# Schema_Electrica.net
KiCad netlist of a schematic drawn in EAGLE
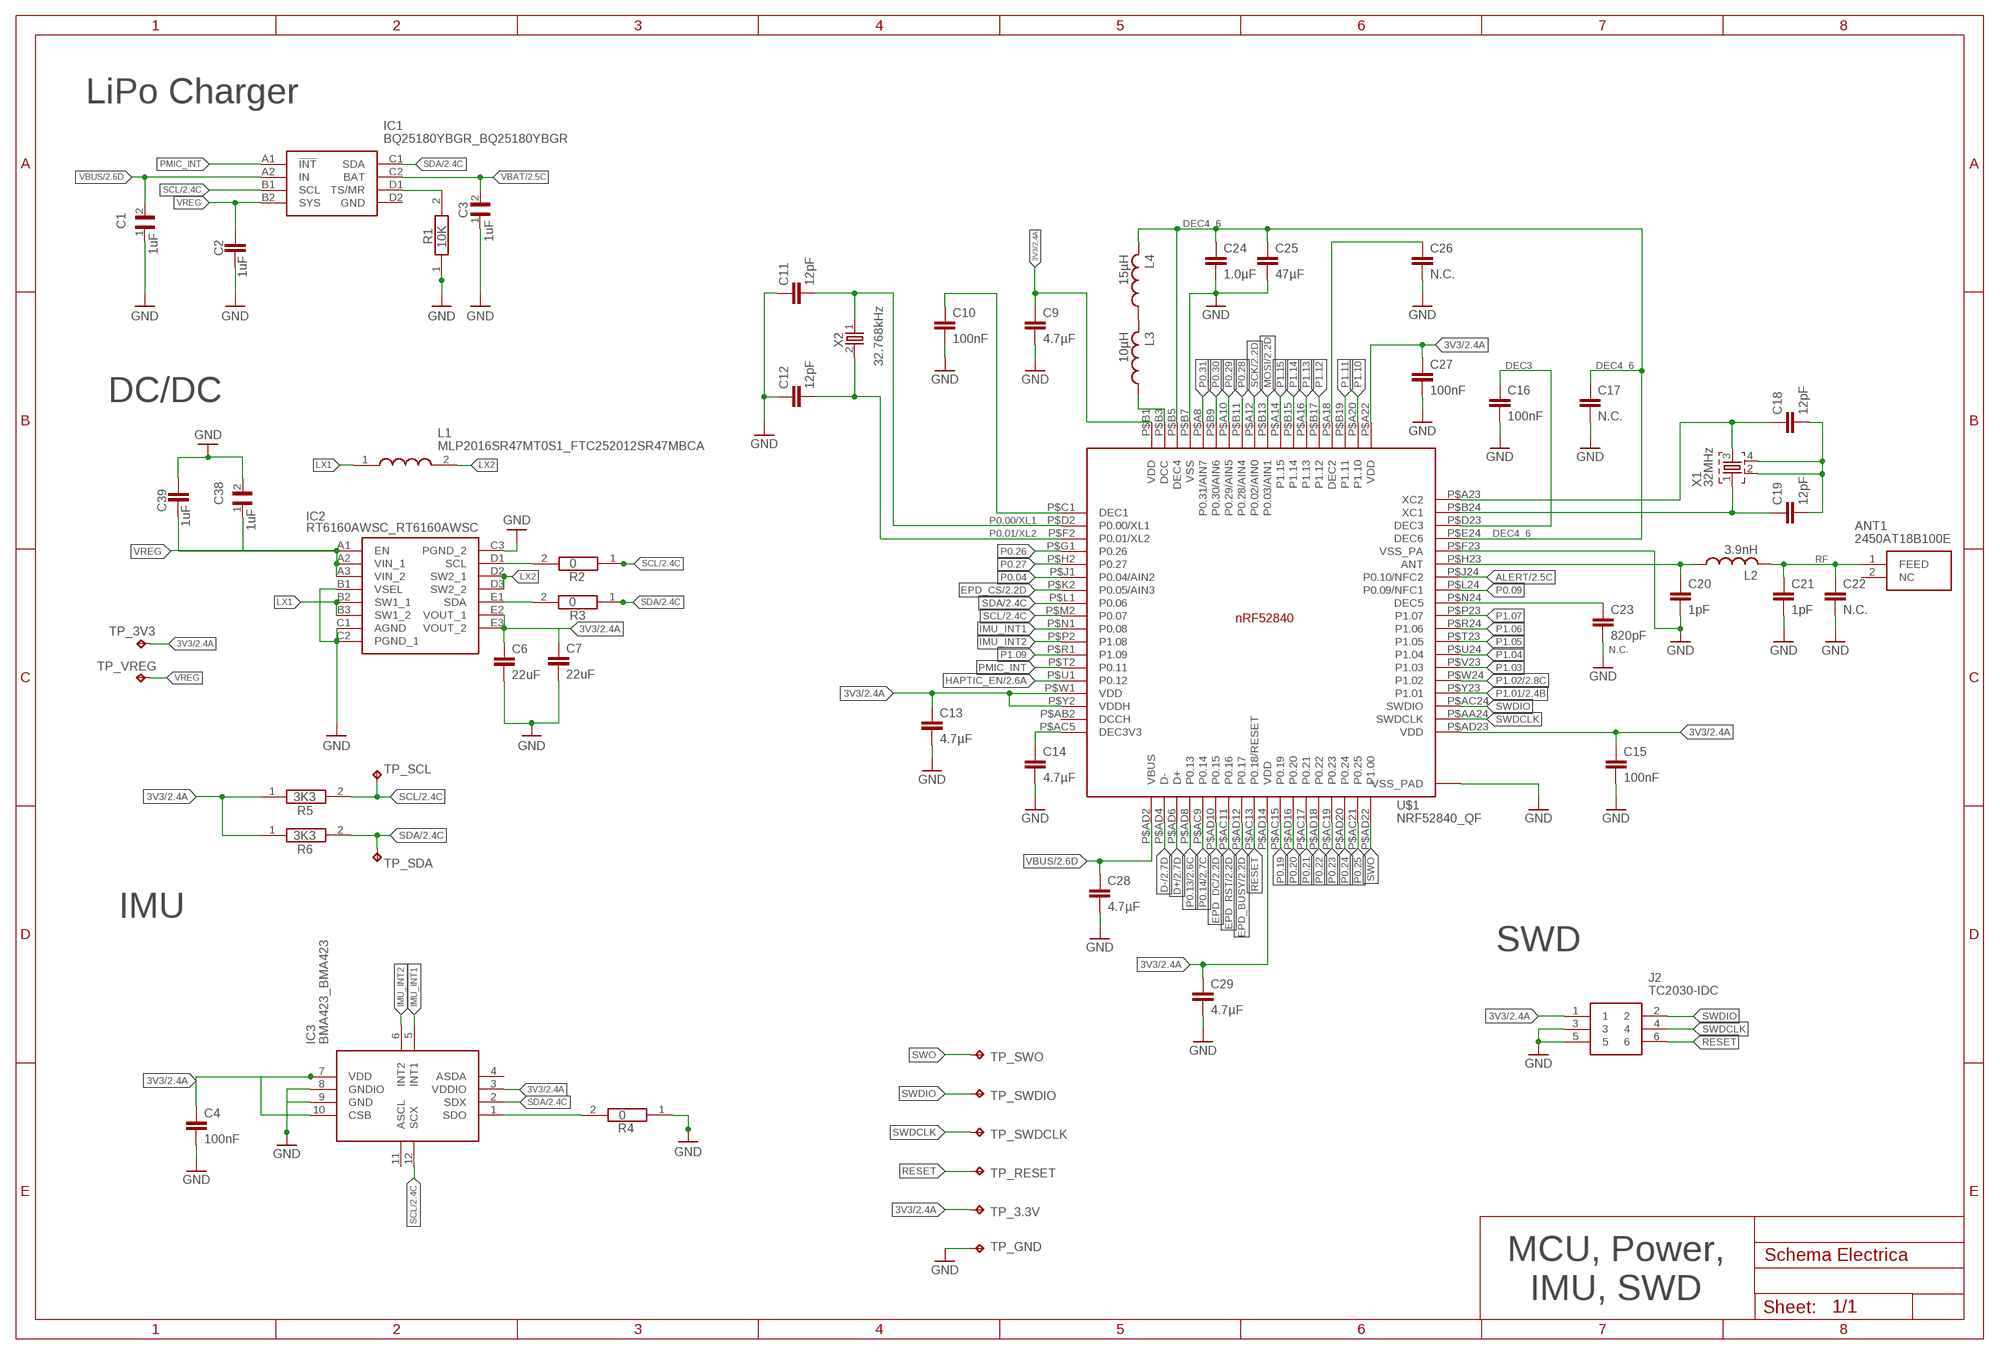
[diagram p0: schematic, sheet 1, part 1 of 2]
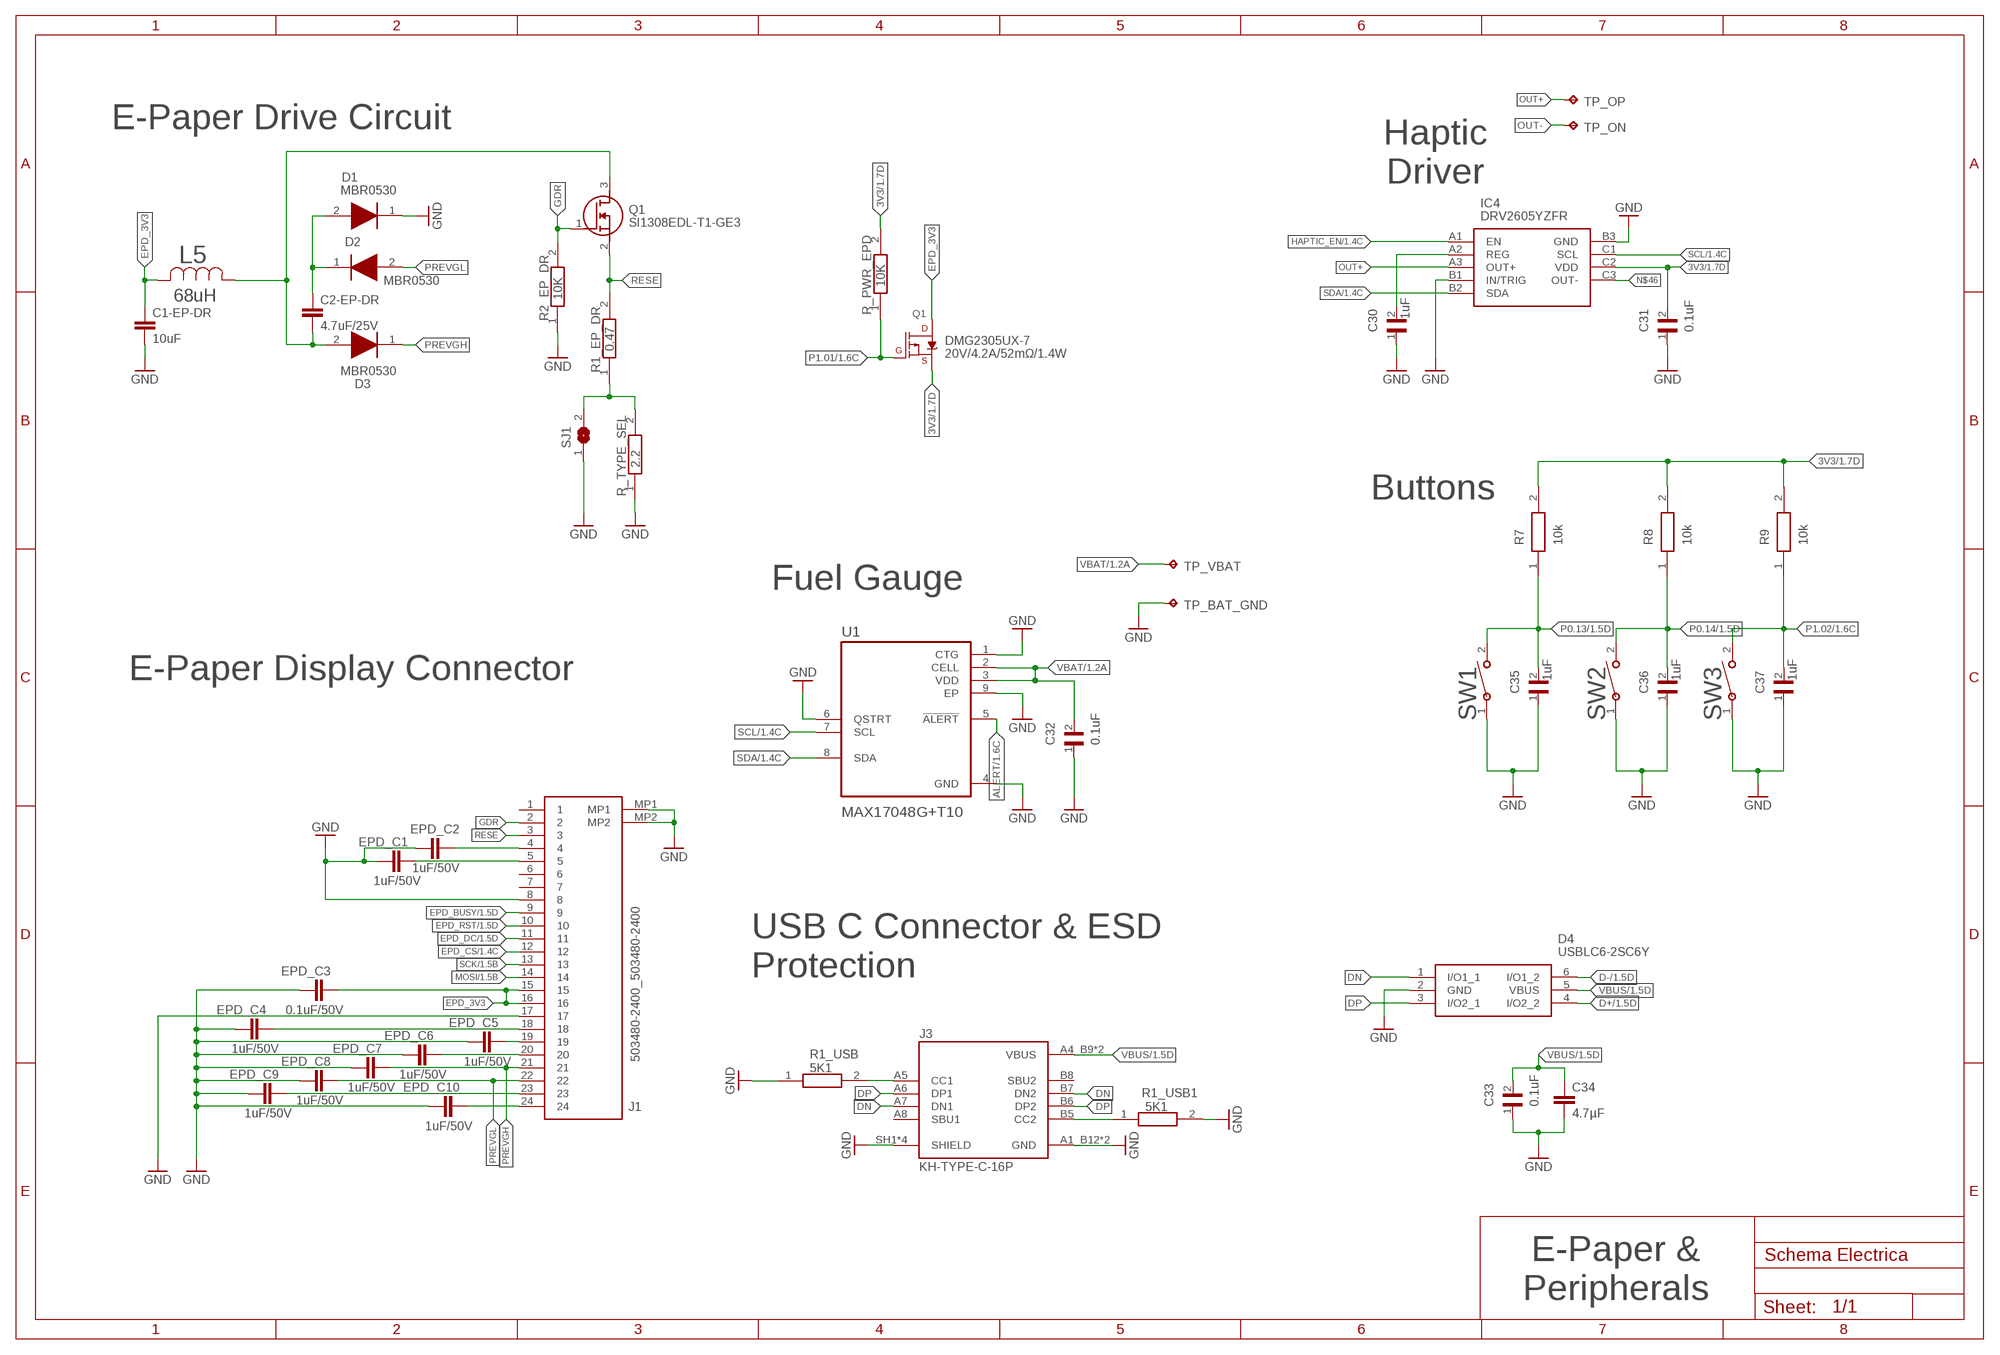
[diagram p1: schematic, sheet 1, part 2 of 2]

(export (version "E")
  (design (tool "Eeschema 10.0.6"))
  (components
    (comp (ref "ANT1")
      (value "2450AT18B100E")
      (footprint "eagle-import:2450AT18B100E_ANTC3216X140N")
      (fields (field (name "MOUSER_PART_NUMBER") "609-2450AT18B100E"))
      (libsource (lib "eagle-import") (part "2450AT18B100E_2450AT18B100E"))
    )
    (comp (ref "C1")
      (value "1uF")
      (footprint "eagle-import:GRM011R60J152KE01L_1_0201")
      (libsource (lib "eagle-import") (part "GRM011R60J152KE01L_1_GRM011R60J152KE01L"))
    )
    (comp (ref "C1-EP-DR")
      (value "10uF")
      (footprint "eagle-import:PERFECT_0402_0402")
      (libsource (lib "eagle-import") (part "PERFECT_0402_CAP_0402"))
    )
    (comp (ref "C2")
      (value "1uF")
      (footprint "eagle-import:PERFECT_0402_0402")
      (libsource (lib "eagle-import") (part "PERFECT_0402_CAP_0402"))
    )
    (comp (ref "C2-EP-DR")
      (value "4.7uF/25V")
      (footprint "eagle-import:PERFECT_0402_0402")
      (libsource (lib "eagle-import") (part "PERFECT_0402_CAP_0402"))
    )
    (comp (ref "C3")
      (value "1uF")
      (footprint "eagle-import:GRM011R60J152KE01L_1_0201")
      (libsource (lib "eagle-import") (part "GRM011R60J152KE01L_1_GRM011R60J152KE01L"))
    )
    (comp (ref "C4")
      (value "100nF")
      (footprint "eagle-import:PERFECT_0402_0402")
      (libsource (lib "eagle-import") (part "PERFECT_0402_CAP_0402"))
    )
    (comp (ref "C6")
      (value "22uF")
      (footprint "eagle-import:PERFECT_0402_0402")
      (libsource (lib "eagle-import") (part "PERFECT_0402_CAP_0402"))
    )
    (comp (ref "C7")
      (value "22uF")
      (footprint "eagle-import:PERFECT_0402_0402")
      (libsource (lib "eagle-import") (part "PERFECT_0402_CAP_0402"))
    )
    (comp (ref "C9")
      (value "4.7µF")
      (footprint "eagle-import:PERFECT_0402_0402")
      (libsource (lib "eagle-import") (part "PERFECT_0402_CAP_0402"))
    )
    (comp (ref "C10")
      (value "100nF")
      (footprint "eagle-import:PERFECT_0402_0402")
      (libsource (lib "eagle-import") (part "PERFECT_0402_CAP_0402"))
    )
    (comp (ref "C11")
      (value "12pF")
      (footprint "eagle-import:PERFECT_0402_0402")
      (libsource (lib "eagle-import") (part "PERFECT_0402_CAP_0402"))
    )
    (comp (ref "C12")
      (value "12pF")
      (footprint "eagle-import:PERFECT_0402_0402")
      (libsource (lib "eagle-import") (part "PERFECT_0402_CAP_0402"))
    )
    (comp (ref "C13")
      (value "4.7µF")
      (footprint "eagle-import:PERFECT_0402_0402")
      (libsource (lib "eagle-import") (part "PERFECT_0402_CAP_0402"))
    )
    (comp (ref "C14")
      (value "4.7µF")
      (footprint "eagle-import:PERFECT_0402_0402")
      (libsource (lib "eagle-import") (part "PERFECT_0402_CAP_0402"))
    )
    (comp (ref "C15")
      (value "100nF")
      (footprint "eagle-import:PERFECT_0402_0402")
      (libsource (lib "eagle-import") (part "PERFECT_0402_CAP_0402"))
    )
    (comp (ref "C16")
      (value "100nF")
      (footprint "eagle-import:PERFECT_0402_0402")
      (libsource (lib "eagle-import") (part "PERFECT_0402_CAP_0402"))
    )
    (comp (ref "C17")
      (value "N.C.")
      (footprint "eagle-import:PERFECT_0402_0402")
      (libsource (lib "eagle-import") (part "PERFECT_0402_CAP_0402"))
    )
    (comp (ref "C18")
      (value "12pF")
      (footprint "eagle-import:PERFECT_0402_0402")
      (libsource (lib "eagle-import") (part "PERFECT_0402_CAP_0402"))
    )
    (comp (ref "C19")
      (value "12pF")
      (footprint "eagle-import:PERFECT_0402_0402")
      (libsource (lib "eagle-import") (part "PERFECT_0402_CAP_0402"))
    )
    (comp (ref "C20")
      (value "1pF")
      (footprint "eagle-import:PERFECT_0402_0402")
      (libsource (lib "eagle-import") (part "PERFECT_0402_CAP_0402"))
    )
    (comp (ref "C21")
      (value "1pF")
      (footprint "eagle-import:PERFECT_0402_0402")
      (libsource (lib "eagle-import") (part "PERFECT_0402_CAP_0402"))
    )
    (comp (ref "C22")
      (value "N.C.")
      (footprint "eagle-import:PERFECT_0402_0402")
      (libsource (lib "eagle-import") (part "PERFECT_0402_CAP_0402"))
    )
    (comp (ref "C23")
      (value "820pF")
      (footprint "eagle-import:PERFECT_0402_0402")
      (libsource (lib "eagle-import") (part "PERFECT_0402_CAP_0402"))
    )
    (comp (ref "C24")
      (value "1.0µF")
      (footprint "eagle-import:PERFECT_0402_0402")
      (libsource (lib "eagle-import") (part "PERFECT_0402_CAP_0402"))
    )
    (comp (ref "C25")
      (value "47µF")
      (footprint "eagle-import:PERFECT_0402_0402")
      (libsource (lib "eagle-import") (part "PERFECT_0402_CAP_0402"))
    )
    (comp (ref "C26")
      (value "N.C.")
      (footprint "eagle-import:PERFECT_0402_0402")
      (libsource (lib "eagle-import") (part "PERFECT_0402_CAP_0402"))
    )
    (comp (ref "C27")
      (value "100nF")
      (footprint "eagle-import:PERFECT_0402_0402")
      (libsource (lib "eagle-import") (part "PERFECT_0402_CAP_0402"))
    )
    (comp (ref "C28")
      (value "4.7µF")
      (footprint "eagle-import:PERFECT_0402_0402")
      (libsource (lib "eagle-import") (part "PERFECT_0402_CAP_0402"))
    )
    (comp (ref "C29")
      (value "4.7µF")
      (footprint "eagle-import:PERFECT_0402_0402")
      (libsource (lib "eagle-import") (part "PERFECT_0402_CAP_0402"))
    )
    (comp (ref "C30")
      (value "1uF")
      (footprint "eagle-import:GRM011R60J152KE01L_1_0201")
      (libsource (lib "eagle-import") (part "GRM011R60J152KE01L_1_GRM011R60J152KE01L"))
    )
    (comp (ref "C31")
      (value "0.1uF")
      (footprint "eagle-import:GRM011R60J152KE01L_1_0201")
      (libsource (lib "eagle-import") (part "GRM011R60J152KE01L_1_GRM011R60J152KE01L"))
    )
    (comp (ref "C32")
      (value "0.1uF")
      (footprint "eagle-import:GRM011R60J152KE01L_1_0201")
      (libsource (lib "eagle-import") (part "GRM011R60J152KE01L_1_GRM011R60J152KE01L"))
    )
    (comp (ref "C33")
      (value "0.1uF")
      (footprint "eagle-import:GRM011R60J152KE01L_1_0201")
      (libsource (lib "eagle-import") (part "GRM011R60J152KE01L_1_GRM011R60J152KE01L"))
    )
    (comp (ref "C34")
      (value "4.7µF")
      (footprint "eagle-import:PERFECT_0402_0402")
      (libsource (lib "eagle-import") (part "PERFECT_0402_CAP_0402"))
    )
    (comp (ref "C35")
      (value "1uF")
      (footprint "eagle-import:GRM011R60J152KE01L_1_0201")
      (libsource (lib "eagle-import") (part "GRM011R60J152KE01L_1_GRM011R60J152KE01L"))
    )
    (comp (ref "C36")
      (value "1uF")
      (footprint "eagle-import:GRM011R60J152KE01L_1_0201")
      (libsource (lib "eagle-import") (part "GRM011R60J152KE01L_1_GRM011R60J152KE01L"))
    )
    (comp (ref "C37")
      (value "1uF")
      (footprint "eagle-import:GRM011R60J152KE01L_1_0201")
      (libsource (lib "eagle-import") (part "GRM011R60J152KE01L_1_GRM011R60J152KE01L"))
    )
    (comp (ref "C38")
      (value "1uF")
      (footprint "eagle-import:GRM011R60J152KE01L_1_0201")
      (libsource (lib "eagle-import") (part "GRM011R60J152KE01L_1_GRM011R60J152KE01L"))
    )
    (comp (ref "C39")
      (value "1uF")
      (footprint "eagle-import:PERFECT_0402_0402")
      (libsource (lib "eagle-import") (part "PERFECT_0402_CAP_0402"))
    )
    (comp (ref "D1")
      (value "MBR0530")
      (footprint "eagle-import:ESP32_C6_LIBRARY_5_SOD3716X135N")
      (fields (field (name "MF") "ON Semiconductor"))
      (libsource (lib "eagle-import") (part "ESP32_C6_LIBRARY_5_MBR0530"))
    )
    (comp (ref "D2")
      (value "MBR0530")
      (footprint "eagle-import:ESP32_C6_LIBRARY_5_SOD3716X135N")
      (fields (field (name "MF") "ON Semiconductor"))
      (libsource (lib "eagle-import") (part "ESP32_C6_LIBRARY_5_MBR0530"))
    )
    (comp (ref "D3")
      (value "MBR0530")
      (footprint "eagle-import:ESP32_C6_LIBRARY_5_SOD3716X135N")
      (fields (field (name "MF") "ON Semiconductor"))
      (libsource (lib "eagle-import") (part "ESP32_C6_LIBRARY_5_MBR0530"))
    )
    (comp (ref "D4")
      (value "USBLC6-2SC6Y")
      (footprint "eagle-import:ESP32_C6_LIBRARY_3_SOT95P280X145-6N")
      (fields (field (name "MF") "STMicroelectronics"))
      (libsource (lib "eagle-import") (part "ESP32_C6_LIBRARY_3_USBLC6-2SC6Y"))
    )
    (comp (ref "DMG2305UX-7")
      (value "20V/4.2A/52mΩ/1.4W")
      (footprint "eagle-import:ESP32_C6_LIBRARY_4_ESP32_C6_LIBRARY_4_ESP32_C6_LIBRARY_4_ESP32_C6_LIBRARY_4_ESP32_WROVER_SPARKFUN-DISCRETESEMI_SOT23-3")
      (libsource (lib "eagle-import") (part "ESP32_C6_LIBRARY_4_ESP32_WROVER_SPARKFUN-DISCRETESEMI_MOSFET_PCH-DMG2305UX-7"))
    )
    (comp (ref "EPD_C1")
      (value "1uF/50V")
      (footprint "eagle-import:PERFECT_0402_0402")
      (libsource (lib "eagle-import") (part "PERFECT_0402_CAP_0402"))
    )
    (comp (ref "EPD_C2")
      (value "1uF/50V")
      (footprint "eagle-import:PERFECT_0402_0402")
      (libsource (lib "eagle-import") (part "PERFECT_0402_CAP_0402"))
    )
    (comp (ref "EPD_C3")
      (value "0.1uF/50V")
      (footprint "eagle-import:PERFECT_0402_0402")
      (libsource (lib "eagle-import") (part "PERFECT_0402_CAP_0402"))
    )
    (comp (ref "EPD_C4")
      (value "1uF/50V")
      (footprint "eagle-import:PERFECT_0402_0402")
      (libsource (lib "eagle-import") (part "PERFECT_0402_CAP_0402"))
    )
    (comp (ref "EPD_C5")
      (value "1uF/50V")
      (footprint "eagle-import:PERFECT_0402_0402")
      (libsource (lib "eagle-import") (part "PERFECT_0402_CAP_0402"))
    )
    (comp (ref "EPD_C6")
      (value "1uF/50V")
      (footprint "eagle-import:PERFECT_0402_0402")
      (libsource (lib "eagle-import") (part "PERFECT_0402_CAP_0402"))
    )
    (comp (ref "EPD_C7")
      (value "1uF/50V")
      (footprint "eagle-import:PERFECT_0402_0402")
      (libsource (lib "eagle-import") (part "PERFECT_0402_CAP_0402"))
    )
    (comp (ref "EPD_C8")
      (value "1uF/50V")
      (footprint "eagle-import:PERFECT_0402_0402")
      (libsource (lib "eagle-import") (part "PERFECT_0402_CAP_0402"))
    )
    (comp (ref "EPD_C9")
      (value "1uF/50V")
      (footprint "eagle-import:PERFECT_0402_0402")
      (libsource (lib "eagle-import") (part "PERFECT_0402_CAP_0402"))
    )
    (comp (ref "EPD_C10")
      (value "1uF/50V")
      (footprint "eagle-import:PERFECT_0402_0402")
      (libsource (lib "eagle-import") (part "PERFECT_0402_CAP_0402"))
    )
    (comp (ref "IC1")
      (value "BQ25180YBGR_BQ25180YBGR")
      (footprint "eagle-import:BQ25180YBGR_BGA8C40P2X4_100X155X50")
      (fields
        (field (name "ARROW_PART_NUMBER") "BQ25180YBGR")
        (field (name "MOUSER_PART_NUMBER") "595-BQ25180YBGR")
      )
      (libsource (lib "eagle-import") (part "BQ25180YBGR_BQ25180YBGR"))
    )
    (comp (ref "IC2")
      (value "RT6160AWSC_RT6160AWSC")
      (footprint "eagle-import:RT6160AWSC_BGA15C40P3X5_140X230X60")
      (fields
        (field (name "MANUFACTURER_PART_NUMBER") "RT6160AWSC")
        (field (name "MOUSER_PART_NUMBER") "835-RT6160AWSC")
      )
      (libsource (lib "eagle-import") (part "RT6160AWSC_RT6160AWSC"))
    )
    (comp (ref "IC3")
      (value "BMA423_BMA423")
      (footprint "eagle-import:BMA423_BMA423")
      (fields (field (name "ARROW_PART_NUMBER") "BMA423") (field (name "MOUSER_PART_NUMBER") "262-BMA423"))
      (libsource (lib "eagle-import") (part "BMA423_BMA423"))
    )
    (comp (ref "IC4")
      (value "DRV2605YZFR")
      (footprint "eagle-import:DRV2605YZFR_BGA9C50P3X3_144X144X62")
      (libsource (lib "eagle-import") (part "DRV2605YZFR_DRV2605YZFR"))
    )
    (comp (ref "J1")
      (value "503480-2400_503480-2400")
      (footprint "eagle-import:503480-2400_5034802400")
      (fields
        (field (name "MANUFACTURER_PART_NUMBER") "503480-2400")
        (field (name "MOUSER_PART_NUMBER") "538-503480-2400")
      )
      (libsource (lib "eagle-import") (part "503480-2400_503480-2400"))
    )
    (comp (ref "J2")
      (value "TC2030-IDC")
      (footprint "eagle-import:TC2030-IDC_TC2030IDC")
      (libsource (lib "eagle-import") (part "TC2030-IDC_TC2030-IDC"))
    )
    (comp (ref "J3")
      (value "KH-TYPE-C-16P")
      (footprint "eagle-import:KH-TYPE-C-16P_KINGHELM_KH-TYPE-C-16P")
      (fields (field (name "MF") "kinghelm"))
      (libsource (lib "eagle-import") (part "KH-TYPE-C-16P_KH-TYPE-C-16P"))
    )
    (comp (ref "L1")
      (value "MLP2016SR47MT0S1_FTC252012SR47MBCA")
      (footprint "eagle-import:MLP2016SR47MT0S1_INDC2016X100N")
      (fields (field (name "MANUFACTURER_PART_NUMBER") "FTC252012SR47MBCA"))
      (libsource (lib "eagle-import") (part "MLP2016SR47MT0S1_FTC252012SR47MBCA"))
    )
    (comp (ref "L2")
      (value "3.9nH")
      (footprint "eagle-import:NORDIC_NRF_2_RESC0402_L")
      (libsource (lib "eagle-import") (part "NORDIC_NRF_2_INDUCTOR_0402_L"))
    )
    (comp (ref "L3")
      (value "10µH")
      (footprint "eagle-import:NORDIC_NRF_2_RESC0402_L")
      (libsource (lib "eagle-import") (part "NORDIC_NRF_2_INDUCTOR_0402_L"))
    )
    (comp (ref "L4")
      (value "15µH")
      (footprint "eagle-import:NORDIC_NRF_2_RESC0402_L")
      (libsource (lib "eagle-import") (part "NORDIC_NRF_2_INDUCTOR_0402_L"))
    )
    (comp (ref "L5")
      (value "68uH")
      (footprint "eagle-import:ESP32_C6_LIBRARY_2_IND_4828-WE-TPC_WRE")
      (fields
        (field (name "MANUFACTURER_PART_NUMBER") "744043680")
        (field (name "COPYRIGHT") "Copyright (C) 2024 Ultra Librarian. All rights reserved.")
      )
      (libsource (lib "eagle-import") (part "ESP32_C6_LIBRARY_2_744043680IND_4828-WE-TPC_WRE"))
    )
    (comp (ref "Q1")
      (value "SI1308EDL-T1-GE3")
      (footprint "eagle-import:ESP32_C6_LIBRARY_6_SOT65P210X110-3N")
      (fields (field (name "MF") "Vishay Siliconix"))
      (libsource (lib "eagle-import") (part "ESP32_C6_LIBRARY_6_SI1308EDL-T1-GE3"))
    )
    (comp (ref "R1")
      (value "10K")
      (footprint "eagle-import:CPF0201D7K68C1_0201")
      (libsource (lib "eagle-import") (part "CPF0201D7K68C1_CPF0201D7K68C1"))
    )
    (comp (ref "R1_EP_DR")
      (value "0.47")
      (footprint "eagle-import:CPF0201D7K68C1_0201")
      (libsource (lib "eagle-import") (part "CPF0201D7K68C1_CPF0201D7K68C1"))
    )
    (comp (ref "R1_USB")
      (value "5K1")
      (footprint "eagle-import:CPF0201D7K68C1_0201")
      (libsource (lib "eagle-import") (part "CPF0201D7K68C1_CPF0201D7K68C1"))
    )
    (comp (ref "R1_USB1")
      (value "5K1")
      (footprint "eagle-import:CPF0201D7K68C1_0201")
      (libsource (lib "eagle-import") (part "CPF0201D7K68C1_CPF0201D7K68C1"))
    )
    (comp (ref "R2")
      (value "0")
      (footprint "eagle-import:CPF0201D7K68C1_0201")
      (libsource (lib "eagle-import") (part "CPF0201D7K68C1_CPF0201D7K68C1"))
    )
    (comp (ref "R2_EP_DR")
      (value "10K")
      (footprint "eagle-import:CPF0201D7K68C1_0201")
      (libsource (lib "eagle-import") (part "CPF0201D7K68C1_CPF0201D7K68C1"))
    )
    (comp (ref "R3")
      (value "0")
      (footprint "eagle-import:CPF0201D7K68C1_0201")
      (libsource (lib "eagle-import") (part "CPF0201D7K68C1_CPF0201D7K68C1"))
    )
    (comp (ref "R4")
      (value "0")
      (footprint "eagle-import:ERA-1AEB3401C_0201")
      (libsource (lib "eagle-import") (part "ERA-1AEB3401C_CPF0201D7K68C1"))
    )
    (comp (ref "R5")
      (value "3K3")
      (footprint "eagle-import:CPF0201D7K68C1_0201")
      (libsource (lib "eagle-import") (part "CPF0201D7K68C1_CPF0201D7K68C1"))
    )
    (comp (ref "R6")
      (value "3K3")
      (footprint "eagle-import:CPF0201D7K68C1_0201")
      (libsource (lib "eagle-import") (part "CPF0201D7K68C1_CPF0201D7K68C1"))
    )
    (comp (ref "R7")
      (value "10k")
      (footprint "eagle-import:ERA-1AEB3401C_0201")
      (libsource (lib "eagle-import") (part "ERA-1AEB3401C_CPF0201D7K68C1"))
    )
    (comp (ref "R8")
      (value "10k")
      (footprint "eagle-import:ERA-1AEB3401C_0201")
      (libsource (lib "eagle-import") (part "ERA-1AEB3401C_CPF0201D7K68C1"))
    )
    (comp (ref "R9")
      (value "10k")
      (footprint "eagle-import:ERA-1AEB3401C_0201")
      (libsource (lib "eagle-import") (part "ERA-1AEB3401C_CPF0201D7K68C1"))
    )
    (comp (ref "R_PWR_EPD")
      (value "10K")
      (footprint "eagle-import:CPF0201D7K68C1_0201")
      (libsource (lib "eagle-import") (part "CPF0201D7K68C1_CPF0201D7K68C1"))
    )
    (comp (ref "R_TYPE_SEL")
      (value "2.2")
      (footprint "eagle-import:CPF0201D7K68C1_0201")
      (libsource (lib "eagle-import") (part "CPF0201D7K68C1_CPF0201D7K68C1"))
    )
    (comp (ref "SJ1")
      (value "ESP32_C6_LIBRARY_7_JUMPER_SJ")
      (footprint "eagle-import:ESP32_C6_LIBRARY_7_JUMPER_SJ")
      (libsource (lib "eagle-import") (part "ESP32_C6_LIBRARY_7_JUMPER_SJ"))
    )
    (comp (ref "SW1")
      (value "2025-10-22_07-23-44_LIBRARY_EVP-AKE31ASW_EVP-AKE31A_PAN")
      (footprint "eagle-import:2025-10-22_07-23-44_LIBRARY_SW_EVP-AKE31A_PAN")
      (fields
        (field (name "MANUFACTURER_PART_NUMBER") "EVP-AKE31A")
        (field (name "COPYRIGHT") "Copyright (C) 2025 Ultra Librarian. All rights reserved.")
      )
      (libsource (lib "eagle-import") (part "2025-10-22_07-23-44_LIBRARY_EVP-AKE31ASW_EVP-AKE31A_PAN"))
    )
    (comp (ref "SW2")
      (value "2025-10-22_07-23-44_LIBRARY_EVP-AKE31ASW_EVP-AKE31A_PAN")
      (footprint "eagle-import:2025-10-22_07-23-44_LIBRARY_SW_EVP-AKE31A_PAN")
      (fields
        (field (name "MANUFACTURER_PART_NUMBER") "EVP-AKE31A")
        (field (name "COPYRIGHT") "Copyright (C) 2025 Ultra Librarian. All rights reserved.")
      )
      (libsource (lib "eagle-import") (part "2025-10-22_07-23-44_LIBRARY_EVP-AKE31ASW_EVP-AKE31A_PAN"))
    )
    (comp (ref "SW3")
      (value "2025-10-22_07-23-44_LIBRARY_EVP-AKE31ASW_EVP-AKE31A_PAN")
      (footprint "eagle-import:2025-10-22_07-23-44_LIBRARY_SW_EVP-AKE31A_PAN")
      (fields
        (field (name "MANUFACTURER_PART_NUMBER") "EVP-AKE31A")
        (field (name "COPYRIGHT") "Copyright (C) 2025 Ultra Librarian. All rights reserved.")
      )
      (libsource (lib "eagle-import") (part "2025-10-22_07-23-44_LIBRARY_EVP-AKE31ASW_EVP-AKE31A_PAN"))
    )
    (comp (ref "TP_3.3V")
      (value "HECTOR_WATCH_1_TPTP20R")
      (footprint "eagle-import:HECTOR_WATCH_1_TP20R")
      (libsource (lib "eagle-import") (part "HECTOR_WATCH_1_TPTP20R"))
    )
    (comp (ref "TP_3V3")
      (value "HECTOR_WATCH_1_TPTP20R")
      (footprint "eagle-import:HECTOR_WATCH_1_TP20R")
      (libsource (lib "eagle-import") (part "HECTOR_WATCH_1_TPTP20R"))
    )
    (comp (ref "TP_BAT_GND")
      (value "HECTOR_WATCH_1_TPTP20R")
      (footprint "eagle-import:HECTOR_WATCH_1_TP20R")
      (libsource (lib "eagle-import") (part "HECTOR_WATCH_1_TPTP20R"))
    )
    (comp (ref "TP_GND")
      (value "HECTOR_WATCH_1_TPTP20R")
      (footprint "eagle-import:HECTOR_WATCH_1_TP20R")
      (libsource (lib "eagle-import") (part "HECTOR_WATCH_1_TPTP20R"))
    )
    (comp (ref "TP_ON")
      (value "HECTOR_WATCH_1_TPTP20R")
      (footprint "eagle-import:HECTOR_WATCH_1_TP20R")
      (libsource (lib "eagle-import") (part "HECTOR_WATCH_1_TPTP20R"))
    )
    (comp (ref "TP_OP")
      (value "HECTOR_WATCH_1_TPTP20R")
      (footprint "eagle-import:HECTOR_WATCH_1_TP20R")
      (libsource (lib "eagle-import") (part "HECTOR_WATCH_1_TPTP20R"))
    )
    (comp (ref "TP_RESET")
      (value "HECTOR_WATCH_1_TPTP20R")
      (footprint "eagle-import:HECTOR_WATCH_1_TP20R")
      (libsource (lib "eagle-import") (part "HECTOR_WATCH_1_TPTP20R"))
    )
    (comp (ref "TP_SCL")
      (value "HECTOR_WATCH_1_TPTP20R")
      (footprint "eagle-import:HECTOR_WATCH_1_TP20R")
      (libsource (lib "eagle-import") (part "HECTOR_WATCH_1_TPTP20R"))
    )
    (comp (ref "TP_SDA")
      (value "HECTOR_WATCH_1_TPTP20R")
      (footprint "eagle-import:HECTOR_WATCH_1_TP20R")
      (libsource (lib "eagle-import") (part "HECTOR_WATCH_1_TPTP20R"))
    )
    (comp (ref "TP_SWDCLK")
      (value "HECTOR_WATCH_1_TPTP20R")
      (footprint "eagle-import:HECTOR_WATCH_1_TP20R")
      (libsource (lib "eagle-import") (part "HECTOR_WATCH_1_TPTP20R"))
    )
    (comp (ref "TP_SWDIO")
      (value "HECTOR_WATCH_1_TPTP20R")
      (footprint "eagle-import:HECTOR_WATCH_1_TP20R")
      (libsource (lib "eagle-import") (part "HECTOR_WATCH_1_TPTP20R"))
    )
    (comp (ref "TP_SWO")
      (value "HECTOR_WATCH_1_TPTP20R")
      (footprint "eagle-import:HECTOR_WATCH_1_TP20R")
      (libsource (lib "eagle-import") (part "HECTOR_WATCH_1_TPTP20R"))
    )
    (comp (ref "TP_VBAT")
      (value "HECTOR_WATCH_1_TPTP20R")
      (footprint "eagle-import:HECTOR_WATCH_1_TP20R")
      (libsource (lib "eagle-import") (part "HECTOR_WATCH_1_TPTP20R"))
    )
    (comp (ref "TP_VREG")
      (value "HECTOR_WATCH_1_TPTP20R")
      (footprint "eagle-import:HECTOR_WATCH_1_TP20R")
      (libsource (lib "eagle-import") (part "HECTOR_WATCH_1_TPTP20R"))
    )
    (comp (ref "U$1")
      (value "NRF52840_QF")
      (footprint "eagle-import:NORDIC_NRF_4_AQFN50P700X700X85_HS-74N")
      (libsource (lib "eagle-import") (part "NORDIC_NRF_4_NRF52840_QF"))
    )
    (comp (ref "U1")
      (value "MAX17048G+T10")
      (footprint "eagle-import:ESP32_C6_LIBRARY_SON50P200X200X80-9N")
      (fields (field (name "MF") "Analog Devices"))
      (libsource (lib "eagle-import") (part "ESP32_C6_LIBRARY_MAX17048G+T10"))
    )
    (comp (ref "X1")
      (value "32MHz")
      (footprint "eagle-import:NORDIC_NRF_BT-XTAL_2016_N")
      (libsource (lib "eagle-import") (part "NORDIC_NRF_XTAL_32MHZ"))
    )
    (comp (ref "X2")
      (value "32.768kHz")
      (footprint "eagle-import:NORDIC_NRF_1_XTAL_3215_N")
      (libsource (lib "eagle-import") (part "NORDIC_NRF_1_XTAL_32KHZ"))
    )
  )
  (nets
    (net (code "1") (name "3V3{slash}1.7D") (class "Default")
      (node (ref "C31") (pin "2") (pinfunction "2_2") (pintype "passive"))
      (node (ref "DMG2305UX-7") (pin "2") (pinfunction "S_2") (pintype "bidirectional"))
      (node (ref "IC4") (pin "C2") (pinfunction "VDD_C2") (pintype "bidirectional"))
      (node (ref "R7") (pin "2") (pinfunction "2_2") (pintype "bidirectional"))
      (node (ref "R8") (pin "2") (pinfunction "2_2") (pintype "bidirectional"))
      (node (ref "R9") (pin "2") (pinfunction "2_2") (pintype "bidirectional"))
      (node (ref "R_PWR_EPD") (pin "2") (pinfunction "2_2") (pintype "bidirectional"))
    )
    (net (code "2") (name "3V3{slash}2.4A") (class "Default")
      (node (ref "C13") (pin "1") (pinfunction "1_1") (pintype "passive"))
      (node (ref "C15") (pin "1") (pinfunction "1_1") (pintype "passive"))
      (node (ref "C27") (pin "1") (pinfunction "1_1") (pintype "passive"))
      (node (ref "C29") (pin "1") (pinfunction "1_1") (pintype "passive"))
      (node (ref "C4") (pin "1") (pinfunction "1_1") (pintype "passive"))
      (node (ref "C6") (pin "1") (pinfunction "1_1") (pintype "passive"))
      (node (ref "C7") (pin "1") (pinfunction "1_1") (pintype "passive"))
      (node (ref "C9") (pin "1") (pinfunction "1_1") (pintype "passive"))
      (node (ref "IC2") (pin "E2") (pinfunction "VOUT_1_E2") (pintype "bidirectional"))
      (node (ref "IC2") (pin "E3") (pinfunction "VOUT_2_E3") (pintype "bidirectional"))
      (node (ref "IC3") (pin "10") (pinfunction "CSB_10") (pintype "bidirectional"))
      (node (ref "IC3") (pin "3") (pinfunction "VDDIO_3") (pintype "bidirectional"))
      (node (ref "IC3") (pin "7") (pinfunction "VDD_7") (pintype "bidirectional"))
      (node (ref "J2") (pin "1") (pinfunction "1_1") (pintype "bidirectional"))
      (node (ref "R5") (pin "1") (pinfunction "1_1") (pintype "bidirectional"))
      (node (ref "R6") (pin "1") (pinfunction "1_1") (pintype "bidirectional"))
      (node (ref "TP_3.3V") (pin "TP") (pinfunction "TP_TP") (pintype "input"))
      (node (ref "TP_3V3") (pin "TP") (pinfunction "TP_TP") (pintype "input"))
      (node (ref "U$1") (pin "P$A22") (pinfunction "VDD_P$A22") (pintype "power_in"))
      (node (ref "U$1") (pin "P$AD14") (pinfunction "VDD_P$AD14") (pintype "power_in"))
      (node (ref "U$1") (pin "P$AD23") (pinfunction "VDD_P$AD23") (pintype "power_in"))
      (node (ref "U$1") (pin "P$B1") (pinfunction "VDD_P$B1") (pintype "power_in"))
      (node (ref "U$1") (pin "P$W1") (pinfunction "VDD_P$W1") (pintype "power_in"))
      (node (ref "U$1") (pin "P$Y2") (pinfunction "VDDH_P$Y2") (pintype "power_in"))
    )
    (net (code "3") (name "ALERT{slash}1.6C") (class "Default")
      (node (ref "U1") (pin "5") (pinfunction "~{ALERT}_5") (pintype "output"))
    )
    (net (code "4") (name "ALERT{slash}2.5C") (class "Default")
      (node (ref "U$1") (pin "P$J24") (pinfunction "P0.10/NFC2_P$J24") (pintype "bidirectional"))
    )
    (net (code "5") (name "D+{slash}1.5D") (class "Default")
      (node (ref "D4") (pin "4") (pinfunction "I/O2_2_4") (pintype "bidirectional"))
    )
    (net (code "6") (name "D+{slash}2.7D") (class "Default")
      (node (ref "U$1") (pin "P$AD6") (pinfunction "D+_P$AD6") (pintype "bidirectional"))
    )
    (net (code "7") (name "D-{slash}1.5D") (class "Default")
      (node (ref "D4") (pin "6") (pinfunction "I/O1_2_6") (pintype "bidirectional"))
    )
    (net (code "8") (name "D-{slash}2.7D") (class "Default")
      (node (ref "U$1") (pin "P$AD4") (pinfunction "D-_P$AD4") (pintype "bidirectional"))
    )
    (net (code "9") (name "DN") (class "Default")
      (node (ref "D4") (pin "1") (pinfunction "I/O1_1_1") (pintype "bidirectional"))
      (node (ref "J3") (pin "A7") (pinfunction "DN1_A7") (pintype "bidirectional"))
      (node (ref "J3") (pin "B7") (pinfunction "DN2_B7") (pintype "bidirectional"))
    )
    (net (code "10") (name "DP") (class "Default")
      (node (ref "D4") (pin "3") (pinfunction "I/O2_1_3") (pintype "bidirectional"))
      (node (ref "J3") (pin "A6") (pinfunction "DP1_A6") (pintype "bidirectional"))
      (node (ref "J3") (pin "B6") (pinfunction "DP2_B6") (pintype "bidirectional"))
    )
    (net (code "11") (name "EPD_3V3") (class "Default")
      (node (ref "C1-EP-DR") (pin "1") (pinfunction "1_1") (pintype "passive"))
      (node (ref "DMG2305UX-7") (pin "3") (pinfunction "D_3") (pintype "bidirectional"))
      (node (ref "EPD_C3") (pin "2") (pinfunction "2_2") (pintype "passive"))
      (node (ref "J1") (pin "15") (pinfunction "15_15") (pintype "bidirectional"))
      (node (ref "J1") (pin "16") (pinfunction "16_16") (pintype "bidirectional"))
      (node (ref "L5") (pin "2") (pinfunction "2_2") (pintype "passive"))
    )
    (net (code "12") (name "EPD_BUSY{slash}1.5D") (class "Default")
      (node (ref "J1") (pin "9") (pinfunction "9_9") (pintype "bidirectional"))
    )
    (net (code "13") (name "EPD_BUSY{slash}2.2D") (class "Default")
      (node (ref "U$1") (pin "P$AD12") (pinfunction "P0.17_P$AD12") (pintype "bidirectional"))
    )
    (net (code "14") (name "EPD_CS{slash}1.4C") (class "Default")
      (node (ref "J1") (pin "12") (pinfunction "12_12") (pintype "bidirectional"))
    )
    (net (code "15") (name "EPD_CS{slash}2.2D") (class "Default")
      (node (ref "U$1") (pin "P$K2") (pinfunction "P0.05/AIN3_P$K2") (pintype "bidirectional"))
    )
    (net (code "16") (name "EPD_DC{slash}1.5D") (class "Default")
      (node (ref "J1") (pin "11") (pinfunction "11_11") (pintype "bidirectional"))
    )
    (net (code "17") (name "EPD_DC{slash}2.2D") (class "Default")
      (node (ref "U$1") (pin "P$AD10") (pinfunction "P0.15_P$AD10") (pintype "bidirectional"))
    )
    (net (code "18") (name "EPD_RST{slash}1.5D") (class "Default")
      (node (ref "J1") (pin "10") (pinfunction "10_10") (pintype "bidirectional"))
    )
    (net (code "19") (name "EPD_RST{slash}2.2D") (class "Default")
      (node (ref "U$1") (pin "P$AC11") (pinfunction "P0.16_P$AC11") (pintype "bidirectional"))
    )
    (net (code "20") (name "GDR") (class "Default")
      (node (ref "J1") (pin "2") (pinfunction "2_2") (pintype "bidirectional"))
      (node (ref "Q1") (pin "1") (pinfunction "G_1") (pintype "bidirectional"))
      (node (ref "R2_EP_DR") (pin "2") (pinfunction "2_2") (pintype "bidirectional"))
    )
    (net (code "21") (name "GND") (class "Default")
      (node (ref "C1") (pin "1") (pinfunction "1_1") (pintype "passive"))
      (node (ref "C1-EP-DR") (pin "2") (pinfunction "2_2") (pintype "passive"))
      (node (ref "C10") (pin "2") (pinfunction "2_2") (pintype "passive"))
      (node (ref "C11") (pin "1") (pinfunction "1_1") (pintype "passive"))
      (node (ref "C12") (pin "1") (pinfunction "1_1") (pintype "passive"))
      (node (ref "C13") (pin "2") (pinfunction "2_2") (pintype "passive"))
      (node (ref "C14") (pin "2") (pinfunction "2_2") (pintype "passive"))
      (node (ref "C15") (pin "2") (pinfunction "2_2") (pintype "passive"))
      (node (ref "C16") (pin "2") (pinfunction "2_2") (pintype "passive"))
      (node (ref "C17") (pin "2") (pinfunction "2_2") (pintype "passive"))
      (node (ref "C2") (pin "2") (pinfunction "2_2") (pintype "passive"))
      (node (ref "C20") (pin "2") (pinfunction "2_2") (pintype "passive"))
      (node (ref "C21") (pin "2") (pinfunction "2_2") (pintype "passive"))
      (node (ref "C22") (pin "2") (pinfunction "2_2") (pintype "passive"))
      (node (ref "C23") (pin "2") (pinfunction "2_2") (pintype "passive"))
      (node (ref "C24") (pin "2") (pinfunction "2_2") (pintype "passive"))
      (node (ref "C25") (pin "2") (pinfunction "2_2") (pintype "passive"))
      (node (ref "C26") (pin "2") (pinfunction "2_2") (pintype "passive"))
      (node (ref "C27") (pin "2") (pinfunction "2_2") (pintype "passive"))
      (node (ref "C28") (pin "2") (pinfunction "2_2") (pintype "passive"))
      (node (ref "C29") (pin "2") (pinfunction "2_2") (pintype "passive"))
      (node (ref "C3") (pin "1") (pinfunction "1_1") (pintype "passive"))
      (node (ref "C30") (pin "1") (pinfunction "1_1") (pintype "passive"))
      (node (ref "C31") (pin "1") (pinfunction "1_1") (pintype "passive"))
      (node (ref "C32") (pin "1") (pinfunction "1_1") (pintype "passive"))
      (node (ref "C33") (pin "1") (pinfunction "1_1") (pintype "passive"))
      (node (ref "C34") (pin "2") (pinfunction "2_2") (pintype "passive"))
      (node (ref "C35") (pin "1") (pinfunction "1_1") (pintype "passive"))
      (node (ref "C36") (pin "1") (pinfunction "1_1") (pintype "passive"))
      (node (ref "C37") (pin "1") (pinfunction "1_1") (pintype "passive"))
      (node (ref "C38") (pin "2") (pinfunction "2_2") (pintype "passive"))
      (node (ref "C39") (pin "1") (pinfunction "1_1") (pintype "passive"))
      (node (ref "C4") (pin "2") (pinfunction "2_2") (pintype "passive"))
      (node (ref "C6") (pin "2") (pinfunction "2_2") (pintype "passive"))
      (node (ref "C7") (pin "2") (pinfunction "2_2") (pintype "passive"))
      (node (ref "C9") (pin "2") (pinfunction "2_2") (pintype "passive"))
      (node (ref "D1") (pin "1") (pinfunction "K_1") (pintype "bidirectional"))
      (node (ref "D4") (pin "2") (pinfunction "GND_2") (pintype "bidirectional"))
      (node (ref "EPD_C1") (pin "1") (pinfunction "1_1") (pintype "passive"))
      (node (ref "EPD_C10") (pin "1") (pinfunction "1_1") (pintype "passive"))
      (node (ref "EPD_C2") (pin "1") (pinfunction "1_1") (pintype "passive"))
      (node (ref "EPD_C3") (pin "1") (pinfunction "1_1") (pintype "passive"))
      (node (ref "EPD_C4") (pin "1") (pinfunction "1_1") (pintype "passive"))
      (node (ref "EPD_C5") (pin "1") (pinfunction "1_1") (pintype "passive"))
      (node (ref "EPD_C6") (pin "1") (pinfunction "1_1") (pintype "passive"))
      (node (ref "EPD_C7") (pin "1") (pinfunction "1_1") (pintype "passive"))
      (node (ref "EPD_C8") (pin "1") (pinfunction "1_1") (pintype "passive"))
      (node (ref "EPD_C9") (pin "1") (pinfunction "1_1") (pintype "passive"))
      (node (ref "IC3") (pin "8") (pinfunction "GNDIO_8") (pintype "bidirectional"))
      (node (ref "IC3") (pin "9") (pinfunction "GND_9") (pintype "bidirectional"))
      (node (ref "IC4") (pin "B1") (pinfunction "IN/TRIG_B1") (pintype "bidirectional"))
      (node (ref "IC4") (pin "B3") (pinfunction "GND_B3") (pintype "bidirectional"))
      (node (ref "J1") (pin "17") (pinfunction "17_17") (pintype "bidirectional"))
      (node (ref "J1") (pin "8") (pinfunction "8_8") (pintype "bidirectional"))
      (node (ref "J1") (pin "MP1") (pinfunction "MP1_MP1") (pintype "bidirectional"))
      (node (ref "J1") (pin "MP2") (pinfunction "MP2_MP2") (pintype "bidirectional"))
      (node (ref "J2") (pin "3") (pinfunction "3_3") (pintype "bidirectional"))
      (node (ref "J2") (pin "5") (pinfunction "5_5") (pintype "bidirectional"))
      (node (ref "J3") (pin "A12_B1") (pinfunction "GND_A12_B1") (pintype "power_in"))
      (node (ref "J3") (pin "A1_B12") (pinfunction "GND_A1_B12") (pintype "power_in"))
      (node (ref "J3") (pin "SH1") (pinfunction "SHIELD_SH1") (pintype "passive"))
      (node (ref "J3") (pin "SH2") (pinfunction "SHIELD_SH2") (pintype "passive"))
      (node (ref "J3") (pin "SH3") (pinfunction "SHIELD_SH3") (pintype "passive"))
      (node (ref "J3") (pin "SH4") (pinfunction "SHIELD_SH4") (pintype "passive"))
      (node (ref "R1") (pin "1") (pinfunction "1_1") (pintype "bidirectional"))
      (node (ref "R1_USB") (pin "1") (pinfunction "1_1") (pintype "bidirectional"))
      (node (ref "R1_USB1") (pin "2") (pinfunction "2_2") (pintype "bidirectional"))
      (node (ref "R2_EP_DR") (pin "1") (pinfunction "1_1") (pintype "bidirectional"))
      (node (ref "R4") (pin "1") (pinfunction "1_1") (pintype "bidirectional"))
      (node (ref "R_TYPE_SEL") (pin "1") (pinfunction "1_1") (pintype "bidirectional"))
      (node (ref "SJ1") (pin "1") (pinfunction "1_1") (pintype "passive"))
      (node (ref "SW1") (pin "1") (pinfunction "1_1") (pintype "passive"))
      (node (ref "SW2") (pin "1") (pinfunction "1_1") (pintype "passive"))
      (node (ref "SW3") (pin "1") (pinfunction "1_1") (pintype "passive"))
      (node (ref "TP_BAT_GND") (pin "TP") (pinfunction "TP_TP") (pintype "input"))
      (node (ref "TP_GND") (pin "TP") (pinfunction "TP_TP") (pintype "input"))
      (node (ref "U$1") (pin "P$74") (pinfunction "VSS_PAD_P$74") (pintype "bidirectional"))
      (node (ref "U$1") (pin "P$75") (pinfunction "VSS_PAD_P$75") (pintype "bidirectional"))
      (node (ref "U$1") (pin "P$76") (pinfunction "VSS_PAD_P$76") (pintype "bidirectional"))
      (node (ref "U$1") (pin "P$77") (pinfunction "VSS_PAD_P$77") (pintype "bidirectional"))
      (node (ref "U$1") (pin "P$78") (pinfunction "VSS_PAD_P$78") (pintype "bidirectional"))
      (node (ref "U$1") (pin "P$79") (pinfunction "VSS_PAD_P$79") (pintype "bidirectional"))
      (node (ref "U$1") (pin "P$80") (pinfunction "VSS_PAD_P$80") (pintype "bidirectional"))
      (node (ref "U$1") (pin "P$81") (pinfunction "VSS_PAD_P$81") (pintype "bidirectional"))
      (node (ref "U$1") (pin "P$82") (pinfunction "VSS_PAD_P$82") (pintype "bidirectional"))
      (node (ref "U$1") (pin "P$83") (pinfunction "VSS_PAD_P$83") (pintype "bidirectional"))
      (node (ref "U$1") (pin "P$84") (pinfunction "VSS_PAD_P$84") (pintype "bidirectional"))
      (node (ref "U$1") (pin "P$85") (pinfunction "VSS_PAD_P$85") (pintype "bidirectional"))
      (node (ref "U$1") (pin "P$86") (pinfunction "VSS_PAD_P$86") (pintype "bidirectional"))
      (node (ref "U$1") (pin "P$87") (pinfunction "VSS_PAD_P$87") (pintype "bidirectional"))
      (node (ref "U$1") (pin "P$88") (pinfunction "VSS_PAD_P$88") (pintype "bidirectional"))
      (node (ref "U$1") (pin "P$89") (pinfunction "VSS_PAD_P$89") (pintype "bidirectional"))
      (node (ref "U$1") (pin "P$90") (pinfunction "VSS_PAD_P$90") (pintype "bidirectional"))
      (node (ref "U$1") (pin "P$B7") (pinfunction "VSS_P$B7") (pintype "power_in"))
      (node (ref "U$1") (pin "P$F23") (pinfunction "VSS_PA_P$F23") (pintype "bidirectional"))
      (node (ref "U1") (pin "1") (pinfunction "CTG_1") (pintype "power_in"))
      (node (ref "U1") (pin "4") (pinfunction "GND_4") (pintype "power_in"))
      (node (ref "U1") (pin "6") (pinfunction "QSTRT_6") (pintype "input"))
      (node (ref "U1") (pin "9") (pinfunction "EP_9") (pintype "power_in"))
    )
    (net (code "22") (name "HAPTIC_EN{slash}1.4C") (class "Default")
      (node (ref "IC4") (pin "A1") (pinfunction "EN_A1") (pintype "bidirectional"))
    )
    (net (code "23") (name "HAPTIC_EN{slash}2.6A") (class "Default")
      (node (ref "U$1") (pin "P$U1") (pinfunction "P0.12_P$U1") (pintype "bidirectional"))
    )
    (net (code "24") (name "IMU_INT1") (class "Default")
      (node (ref "IC3") (pin "5") (pinfunction "INT1_5") (pintype "bidirectional"))
      (node (ref "U$1") (pin "P$N1") (pinfunction "P0.08_P$N1") (pintype "bidirectional"))
    )
    (net (code "25") (name "IMU_INT2") (class "Default")
      (node (ref "IC3") (pin "6") (pinfunction "INT2_6") (pintype "bidirectional"))
      (node (ref "U$1") (pin "P$P2") (pinfunction "P1.08_P$P2") (pintype "bidirectional"))
    )
    (net (code "26") (name "LX1") (class "Default")
      (node (ref "IC2") (pin "B2") (pinfunction "SW1_1_B2") (pintype "bidirectional"))
      (node (ref "IC2") (pin "B3") (pinfunction "SW1_2_B3") (pintype "bidirectional"))
      (node (ref "L1") (pin "1") (pinfunction "1_1") (pintype "bidirectional"))
    )
    (net (code "27") (name "LX2") (class "Default")
      (node (ref "IC2") (pin "D2") (pinfunction "SW2_1_D2") (pintype "bidirectional"))
      (node (ref "IC2") (pin "D3") (pinfunction "SW2_2_D3") (pintype "bidirectional"))
      (node (ref "L1") (pin "2") (pinfunction "2_2") (pintype "bidirectional"))
    )
    (net (code "28") (name "MOSI{slash}1.5B") (class "Default")
      (node (ref "J1") (pin "14") (pinfunction "14_14") (pintype "bidirectional"))
    )
    (net (code "29") (name "MOSI{slash}2.2D") (class "Default")
      (node (ref "U$1") (pin "P$B13") (pinfunction "P0.03/AIN1_P$B13") (pintype "bidirectional"))
    )
    (net (code "30") (name "N$46") (class "Default")
      (node (ref "IC4") (pin "C3") (pinfunction "OUT-_C3") (pintype "bidirectional"))
    )
    (net (code "31") (name "Net-(ANT1-FEED)") (class "Default")
      (node (ref "ANT1") (pin "1") (pinfunction "FEED_1") (pintype "input"))
      (node (ref "C21") (pin "1") (pinfunction "1_1") (pintype "passive"))
      (node (ref "C22") (pin "1") (pinfunction "1_1") (pintype "passive"))
      (node (ref "L2") (pin "2") (pinfunction "2_2") (pintype "passive"))
    )
    (net (code "32") (name "Net-(C18-Pad2)") (class "Default")
      (node (ref "C18") (pin "2") (pinfunction "2_2") (pintype "passive"))
      (node (ref "C19") (pin "2") (pinfunction "2_2") (pintype "passive"))
      (node (ref "X1") (pin "2") (pinfunction "2_2") (pintype "passive"))
      (node (ref "X1") (pin "4") (pinfunction "4_4") (pintype "passive"))
    )
    (net (code "33") (name "Net-(D1-A)") (class "Default")
      (node (ref "C2-EP-DR") (pin "1") (pinfunction "1_1") (pintype "passive"))
      (node (ref "D1") (pin "2") (pinfunction "A_2") (pintype "bidirectional"))
      (node (ref "D2") (pin "1") (pinfunction "K_1") (pintype "bidirectional"))
    )
    (net (code "34") (name "Net-(D3-A)") (class "Default")
      (node (ref "C2-EP-DR") (pin "2") (pinfunction "2_2") (pintype "passive"))
      (node (ref "D3") (pin "2") (pinfunction "A_2") (pintype "bidirectional"))
      (node (ref "L5") (pin "1") (pinfunction "1_1") (pintype "passive"))
      (node (ref "Q1") (pin "3") (pinfunction "D_3") (pintype "bidirectional"))
    )
    (net (code "35") (name "Net-(EPD_C1-Pad2)") (class "Default")
      (node (ref "EPD_C1") (pin "2") (pinfunction "2_2") (pintype "passive"))
      (node (ref "J1") (pin "5") (pinfunction "5_5") (pintype "bidirectional"))
    )
    (net (code "36") (name "Net-(EPD_C2-Pad2)") (class "Default")
      (node (ref "EPD_C2") (pin "2") (pinfunction "2_2") (pintype "passive"))
      (node (ref "J1") (pin "4") (pinfunction "4_4") (pintype "bidirectional"))
    )
    (net (code "37") (name "Net-(EPD_C4-Pad2)") (class "Default")
      (node (ref "EPD_C4") (pin "2") (pinfunction "2_2") (pintype "passive"))
      (node (ref "J1") (pin "18") (pinfunction "18_18") (pintype "bidirectional"))
    )
    (net (code "38") (name "Net-(EPD_C5-Pad2)") (class "Default")
      (node (ref "EPD_C5") (pin "2") (pinfunction "2_2") (pintype "passive"))
      (node (ref "J1") (pin "19") (pinfunction "19_19") (pintype "bidirectional"))
    )
    (net (code "39") (name "Net-(EPD_C6-Pad2)") (class "Default")
      (node (ref "EPD_C6") (pin "2") (pinfunction "2_2") (pintype "passive"))
      (node (ref "J1") (pin "20") (pinfunction "20_20") (pintype "bidirectional"))
    )
    (net (code "40") (name "Net-(EPD_C9-Pad2)") (class "Default")
      (node (ref "EPD_C9") (pin "2") (pinfunction "2_2") (pintype "passive"))
      (node (ref "J1") (pin "23") (pinfunction "23_23") (pintype "bidirectional"))
    )
    (net (code "41") (name "Net-(EPD_C10-Pad2)") (class "Default")
      (node (ref "EPD_C10") (pin "2") (pinfunction "2_2") (pintype "passive"))
      (node (ref "J1") (pin "24") (pinfunction "24_24") (pintype "bidirectional"))
    )
    (net (code "42") (name "Net-(IC1-TS{slash}MR)") (class "Default")
      (node (ref "IC1") (pin "D1") (pinfunction "TS/MR_D1") (pintype "bidirectional"))
      (node (ref "R1") (pin "2") (pinfunction "2_2") (pintype "bidirectional"))
    )
    (net (code "43") (name "Net-(IC2-AGND)") (class "Default")
      (node (ref "IC2") (pin "B1") (pinfunction "VSEL_B1") (pintype "bidirectional"))
      (node (ref "IC2") (pin "C1") (pinfunction "AGND_C1") (pintype "bidirectional"))
      (node (ref "IC2") (pin "C2") (pinfunction "PGND_1_C2") (pintype "bidirectional"))
    )
    (net (code "44") (name "Net-(IC2-SCL)") (class "Default")
      (node (ref "IC2") (pin "D1") (pinfunction "SCL_D1") (pintype "bidirectional"))
      (node (ref "R2") (pin "2") (pinfunction "2_2") (pintype "bidirectional"))
    )
    (net (code "45") (name "Net-(IC2-SDA)") (class "Default")
      (node (ref "IC2") (pin "E1") (pinfunction "SDA_E1") (pintype "bidirectional"))
      (node (ref "R3") (pin "2") (pinfunction "2_2") (pintype "bidirectional"))
    )
    (net (code "46") (name "Net-(IC3-SDO)") (class "Default")
      (node (ref "IC3") (pin "1") (pinfunction "SDO_1") (pintype "bidirectional"))
      (node (ref "R4") (pin "2") (pinfunction "2_2") (pintype "bidirectional"))
    )
    (net (code "47") (name "Net-(IC4-REG)") (class "Default")
      (node (ref "C30") (pin "2") (pinfunction "2_2") (pintype "passive"))
      (node (ref "IC4") (pin "A2") (pinfunction "REG_A2") (pintype "bidirectional"))
    )
    (net (code "48") (name "Net-(J3-CC1)") (class "Default")
      (node (ref "J3") (pin "A5") (pinfunction "CC1_A5") (pintype "bidirectional"))
      (node (ref "R1_USB") (pin "2") (pinfunction "2_2") (pintype "bidirectional"))
    )
    (net (code "49") (name "Net-(J3-CC2)") (class "Default")
      (node (ref "J3") (pin "B5") (pinfunction "CC2_B5") (pintype "bidirectional"))
      (node (ref "R1_USB1") (pin "1") (pinfunction "1_1") (pintype "bidirectional"))
    )
    (net (code "50") (name "Net-(L3-Pad2)") (class "Default")
      (node (ref "L3") (pin "2") (pinfunction "2_2") (pintype "passive"))
      (node (ref "L4") (pin "1") (pinfunction "1_1") (pintype "passive"))
    )
    (net (code "51") (name "Net-(R1_EP_DR-Pad1)") (class "Default")
      (node (ref "R1_EP_DR") (pin "1") (pinfunction "1_1") (pintype "bidirectional"))
      (node (ref "R_TYPE_SEL") (pin "2") (pinfunction "2_2") (pintype "bidirectional"))
      (node (ref "SJ1") (pin "2") (pinfunction "2_2") (pintype "passive"))
    )
    (net (code "52") (name "Net-(U$1-ANT)") (class "Default")
      (node (ref "C20") (pin "1") (pinfunction "1_1") (pintype "passive"))
      (node (ref "L2") (pin "1") (pinfunction "1_1") (pintype "passive"))
      (node (ref "U$1") (pin "P$H23") (pinfunction "ANT_P$H23") (pintype "bidirectional"))
    )
    (net (code "53") (name "Net-(U$1-DCC)") (class "Default")
      (node (ref "L3") (pin "1") (pinfunction "1_1") (pintype "passive"))
      (node (ref "U$1") (pin "P$B3") (pinfunction "DCC_P$B3") (pintype "output"))
    )
    (net (code "54") (name "Net-(U$1-DEC1)") (class "Default")
      (node (ref "C10") (pin "1") (pinfunction "1_1") (pintype "passive"))
      (node (ref "U$1") (pin "P$C1") (pinfunction "DEC1_P$C1") (pintype "power_in"))
    )
    (net (code "55") (name "Net-(U$1-DEC2)") (class "Default")
      (node (ref "C26") (pin "1") (pinfunction "1_1") (pintype "passive"))
      (node (ref "U$1") (pin "P$A18") (pinfunction "DEC2_P$A18") (pintype "bidirectional"))
    )
    (net (code "56") (name "Net-(U$1-DEC3)") (class "Default")
      (node (ref "C16") (pin "1") (pinfunction "1_1") (pintype "passive"))
      (node (ref "U$1") (pin "P$D23") (pinfunction "DEC3_P$D23") (pintype "bidirectional"))
    )
    (net (code "57") (name "Net-(U$1-DEC3V3)") (class "Default")
      (node (ref "C14") (pin "1") (pinfunction "1_1") (pintype "passive"))
      (node (ref "U$1") (pin "P$AC5") (pinfunction "DEC3V3_P$AC5") (pintype "bidirectional"))
    )
    (net (code "58") (name "Net-(U$1-DEC4)") (class "Default")
      (node (ref "C17") (pin "1") (pinfunction "1_1") (pintype "passive"))
      (node (ref "C24") (pin "1") (pinfunction "1_1") (pintype "passive"))
      (node (ref "C25") (pin "1") (pinfunction "1_1") (pintype "passive"))
      (node (ref "L4") (pin "2") (pinfunction "2_2") (pintype "passive"))
      (node (ref "U$1") (pin "P$B5") (pinfunction "DEC4_P$B5") (pintype "power_in"))
      (node (ref "U$1") (pin "P$E24") (pinfunction "DEC6_P$E24") (pintype "bidirectional"))
    )
    (net (code "59") (name "Net-(U$1-DEC5)") (class "Default")
      (node (ref "C23") (pin "1") (pinfunction "1_1") (pintype "passive"))
      (node (ref "U$1") (pin "P$N24") (pinfunction "DEC5_P$N24") (pintype "bidirectional"))
    )
    (net (code "60") (name "Net-(U$1-P0.00{slash}XL1)") (class "Default")
      (node (ref "C11") (pin "2") (pinfunction "2_2") (pintype "passive"))
      (node (ref "U$1") (pin "P$D2") (pinfunction "P0.00/XL1_P$D2") (pintype "bidirectional"))
      (node (ref "X2") (pin "1") (pinfunction "1_1") (pintype "passive"))
    )
    (net (code "61") (name "Net-(U$1-P0.01{slash}XL2)") (class "Default")
      (node (ref "C12") (pin "2") (pinfunction "2_2") (pintype "passive"))
      (node (ref "U$1") (pin "P$F2") (pinfunction "P0.01/XL2_P$F2") (pintype "bidirectional"))
      (node (ref "X2") (pin "2") (pinfunction "2_2") (pintype "passive"))
    )
    (net (code "62") (name "Net-(U$1-XC1)") (class "Default")
      (node (ref "C19") (pin "1") (pinfunction "1_1") (pintype "passive"))
      (node (ref "U$1") (pin "P$B24") (pinfunction "XC1_P$B24") (pintype "input"))
      (node (ref "X1") (pin "1") (pinfunction "1_1") (pintype "passive"))
    )
    (net (code "63") (name "Net-(U$1-XC2)") (class "Default")
      (node (ref "C18") (pin "1") (pinfunction "1_1") (pintype "passive"))
      (node (ref "U$1") (pin "P$A23") (pinfunction "XC2_P$A23") (pintype "output"))
      (node (ref "X1") (pin "3") (pinfunction "3_3") (pintype "passive"))
    )
    (net (code "64") (name "OUT+") (class "Default")
      (node (ref "IC4") (pin "A3") (pinfunction "OUT+_A3") (pintype "bidirectional"))
      (node (ref "TP_OP") (pin "TP") (pinfunction "TP_TP") (pintype "input"))
    )
    (net (code "65") (name "OUT-") (class "Default")
      (node (ref "TP_ON") (pin "TP") (pinfunction "TP_TP") (pintype "input"))
    )
    (net (code "66") (name "P0.04") (class "Default")
      (node (ref "U$1") (pin "P$J1") (pinfunction "P0.04/AIN2_P$J1") (pintype "bidirectional"))
    )
    (net (code "67") (name "P0.09") (class "Default")
      (node (ref "U$1") (pin "P$L24") (pinfunction "P0.09/NFC1_P$L24") (pintype "bidirectional"))
    )
    (net (code "68") (name "P0.13{slash}1.5D") (class "Default")
      (node (ref "C35") (pin "2") (pinfunction "2_2") (pintype "passive"))
      (node (ref "R7") (pin "1") (pinfunction "1_1") (pintype "bidirectional"))
      (node (ref "SW1") (pin "2") (pinfunction "2_2") (pintype "passive"))
    )
    (net (code "69") (name "P0.13{slash}2.6C") (class "Default")
      (node (ref "U$1") (pin "P$AD8") (pinfunction "P0.13_P$AD8") (pintype "bidirectional"))
    )
    (net (code "70") (name "P0.14{slash}1.5D") (class "Default")
      (node (ref "C36") (pin "2") (pinfunction "2_2") (pintype "passive"))
      (node (ref "R8") (pin "1") (pinfunction "1_1") (pintype "bidirectional"))
      (node (ref "SW2") (pin "2") (pinfunction "2_2") (pintype "passive"))
    )
    (net (code "71") (name "P0.14{slash}2.7C") (class "Default")
      (node (ref "U$1") (pin "P$AC9") (pinfunction "P0.14_P$AC9") (pintype "bidirectional"))
    )
    (net (code "72") (name "P0.19") (class "Default")
      (node (ref "U$1") (pin "P$AC15") (pinfunction "P0.19_P$AC15") (pintype "bidirectional"))
    )
    (net (code "73") (name "P0.20") (class "Default")
      (node (ref "U$1") (pin "P$AD16") (pinfunction "P0.20_P$AD16") (pintype "bidirectional"))
    )
    (net (code "74") (name "P0.21") (class "Default")
      (node (ref "U$1") (pin "P$AC17") (pinfunction "P0.21_P$AC17") (pintype "bidirectional"))
    )
    (net (code "75") (name "P0.22") (class "Default")
      (node (ref "U$1") (pin "P$AD18") (pinfunction "P0.22_P$AD18") (pintype "bidirectional"))
    )
    (net (code "76") (name "P0.23") (class "Default")
      (node (ref "U$1") (pin "P$AC19") (pinfunction "P0.23_P$AC19") (pintype "bidirectional"))
    )
    (net (code "77") (name "P0.24") (class "Default")
      (node (ref "U$1") (pin "P$AD20") (pinfunction "P0.24_P$AD20") (pintype "bidirectional"))
    )
    (net (code "78") (name "P0.25") (class "Default")
      (node (ref "U$1") (pin "P$AC21") (pinfunction "P0.25_P$AC21") (pintype "bidirectional"))
    )
    (net (code "79") (name "P0.26") (class "Default")
      (node (ref "U$1") (pin "P$G1") (pinfunction "P0.26_P$G1") (pintype "bidirectional"))
    )
    (net (code "80") (name "P0.27") (class "Default")
      (node (ref "U$1") (pin "P$H2") (pinfunction "P0.27_P$H2") (pintype "bidirectional"))
    )
    (net (code "81") (name "P0.28") (class "Default")
      (node (ref "U$1") (pin "P$B11") (pinfunction "P0.28/AIN4_P$B11") (pintype "bidirectional"))
    )
    (net (code "82") (name "P0.29") (class "Default")
      (node (ref "U$1") (pin "P$A10") (pinfunction "P0.29/AIN5_P$A10") (pintype "bidirectional"))
    )
    (net (code "83") (name "P0.30") (class "Default")
      (node (ref "U$1") (pin "P$B9") (pinfunction "P0.30/AIN6_P$B9") (pintype "bidirectional"))
    )
    (net (code "84") (name "P0.31") (class "Default")
      (node (ref "U$1") (pin "P$A8") (pinfunction "P0.31/AIN7_P$A8") (pintype "bidirectional"))
    )
    (net (code "85") (name "P1.01{slash}1.6C") (class "Default")
      (node (ref "DMG2305UX-7") (pin "1") (pinfunction "G_1") (pintype "bidirectional"))
      (node (ref "R_PWR_EPD") (pin "1") (pinfunction "1_1") (pintype "bidirectional"))
    )
    (net (code "86") (name "P1.01{slash}2.4B") (class "Default")
      (node (ref "U$1") (pin "P$Y23") (pinfunction "P1.01_P$Y23") (pintype "bidirectional"))
    )
    (net (code "87") (name "P1.02{slash}1.6C") (class "Default")
      (node (ref "C37") (pin "2") (pinfunction "2_2") (pintype "passive"))
      (node (ref "R9") (pin "1") (pinfunction "1_1") (pintype "bidirectional"))
      (node (ref "SW3") (pin "2") (pinfunction "2_2") (pintype "passive"))
    )
    (net (code "88") (name "P1.02{slash}2.8C") (class "Default")
      (node (ref "U$1") (pin "P$W24") (pinfunction "P1.02_P$W24") (pintype "bidirectional"))
    )
    (net (code "89") (name "P1.03") (class "Default")
      (node (ref "U$1") (pin "P$V23") (pinfunction "P1.03_P$V23") (pintype "bidirectional"))
    )
    (net (code "90") (name "P1.04") (class "Default")
      (node (ref "U$1") (pin "P$U24") (pinfunction "P1.04_P$U24") (pintype "bidirectional"))
    )
    (net (code "91") (name "P1.05") (class "Default")
      (node (ref "U$1") (pin "P$T23") (pinfunction "P1.05_P$T23") (pintype "bidirectional"))
    )
    (net (code "92") (name "P1.06") (class "Default")
      (node (ref "U$1") (pin "P$R24") (pinfunction "P1.06_P$R24") (pintype "bidirectional"))
    )
    (net (code "93") (name "P1.07") (class "Default")
      (node (ref "U$1") (pin "P$P23") (pinfunction "P1.07_P$P23") (pintype "bidirectional"))
    )
    (net (code "94") (name "P1.09") (class "Default")
      (node (ref "U$1") (pin "P$R1") (pinfunction "P1.09_P$R1") (pintype "bidirectional"))
    )
    (net (code "95") (name "P1.10") (class "Default")
      (node (ref "U$1") (pin "P$A20") (pinfunction "P1.10_P$A20") (pintype "bidirectional"))
    )
    (net (code "96") (name "P1.11") (class "Default")
      (node (ref "U$1") (pin "P$B19") (pinfunction "P1.11_P$B19") (pintype "bidirectional"))
    )
    (net (code "97") (name "P1.12") (class "Default")
      (node (ref "U$1") (pin "P$B17") (pinfunction "P1.12_P$B17") (pintype "bidirectional"))
    )
    (net (code "98") (name "P1.13") (class "Default")
      (node (ref "U$1") (pin "P$A16") (pinfunction "P1.13_P$A16") (pintype "bidirectional"))
    )
    (net (code "99") (name "P1.14") (class "Default")
      (node (ref "U$1") (pin "P$B15") (pinfunction "P1.14_P$B15") (pintype "bidirectional"))
    )
    (net (code "100") (name "P1.15") (class "Default")
      (node (ref "U$1") (pin "P$A14") (pinfunction "P1.15_P$A14") (pintype "bidirectional"))
    )
    (net (code "101") (name "PMIC_INT") (class "Default")
      (node (ref "IC1") (pin "A1") (pinfunction "~{INT}_A1") (pintype "bidirectional"))
      (node (ref "U$1") (pin "P$T2") (pinfunction "P0.11_P$T2") (pintype "bidirectional"))
    )
    (net (code "102") (name "PREVGH") (class "Default")
      (node (ref "D3") (pin "1") (pinfunction "K_1") (pintype "bidirectional"))
      (node (ref "EPD_C7") (pin "2") (pinfunction "2_2") (pintype "passive"))
      (node (ref "J1") (pin "21") (pinfunction "21_21") (pintype "bidirectional"))
    )
    (net (code "103") (name "PREVGL") (class "Default")
      (node (ref "D2") (pin "2") (pinfunction "A_2") (pintype "bidirectional"))
      (node (ref "EPD_C8") (pin "2") (pinfunction "2_2") (pintype "passive"))
      (node (ref "J1") (pin "22") (pinfunction "22_22") (pintype "bidirectional"))
    )
    (net (code "104") (name "RESE") (class "Default")
      (node (ref "J1") (pin "3") (pinfunction "3_3") (pintype "bidirectional"))
      (node (ref "Q1") (pin "2") (pinfunction "S_2") (pintype "bidirectional"))
      (node (ref "R1_EP_DR") (pin "2") (pinfunction "2_2") (pintype "bidirectional"))
    )
    (net (code "105") (name "RESET") (class "Default")
      (node (ref "J2") (pin "6") (pinfunction "6_6") (pintype "bidirectional"))
      (node (ref "TP_RESET") (pin "TP") (pinfunction "TP_TP") (pintype "input"))
      (node (ref "U$1") (pin "P$AC13") (pinfunction "P0.18/RESET_P$AC13") (pintype "bidirectional"))
    )
    (net (code "106") (name "SCK{slash}1.5B") (class "Default")
      (node (ref "J1") (pin "13") (pinfunction "13_13") (pintype "bidirectional"))
    )
    (net (code "107") (name "SCK{slash}2.2D") (class "Default")
      (node (ref "U$1") (pin "P$A12") (pinfunction "P0.02/AIN0_P$A12") (pintype "bidirectional"))
    )
    (net (code "108") (name "SCL{slash}1.4C") (class "Default")
      (node (ref "IC4") (pin "C1") (pinfunction "SCL_C1") (pintype "bidirectional"))
      (node (ref "U1") (pin "7") (pinfunction "SCL_7") (pintype "input"))
    )
    (net (code "109") (name "SCL{slash}2.4C") (class "Default")
      (node (ref "IC1") (pin "B1") (pinfunction "SCL_B1") (pintype "bidirectional"))
      (node (ref "IC3") (pin "12") (pinfunction "SCX_12") (pintype "bidirectional"))
      (node (ref "R2") (pin "1") (pinfunction "1_1") (pintype "bidirectional"))
      (node (ref "R5") (pin "2") (pinfunction "2_2") (pintype "bidirectional"))
      (node (ref "TP_SCL") (pin "TP") (pinfunction "TP_TP") (pintype "input"))
      (node (ref "U$1") (pin "P$M2") (pinfunction "P0.07_P$M2") (pintype "bidirectional"))
    )
    (net (code "110") (name "SDA{slash}1.4C") (class "Default")
      (node (ref "IC4") (pin "B2") (pinfunction "SDA_B2") (pintype "bidirectional"))
      (node (ref "U1") (pin "8") (pinfunction "SDA_8") (pintype "bidirectional"))
    )
    (net (code "111") (name "SDA{slash}2.4C") (class "Default")
      (node (ref "IC1") (pin "C1") (pinfunction "SDA_C1") (pintype "bidirectional"))
      (node (ref "IC3") (pin "2") (pinfunction "SDX_2") (pintype "bidirectional"))
      (node (ref "R3") (pin "1") (pinfunction "1_1") (pintype "bidirectional"))
      (node (ref "R6") (pin "2") (pinfunction "2_2") (pintype "bidirectional"))
      (node (ref "TP_SDA") (pin "TP") (pinfunction "TP_TP") (pintype "input"))
      (node (ref "U$1") (pin "P$L1") (pinfunction "P0.06_P$L1") (pintype "bidirectional"))
    )
    (net (code "112") (name "SWDCLK") (class "Default")
      (node (ref "J2") (pin "4") (pinfunction "4_4") (pintype "bidirectional"))
      (node (ref "TP_SWDCLK") (pin "TP") (pinfunction "TP_TP") (pintype "input"))
      (node (ref "U$1") (pin "P$AA24") (pinfunction "SWDCLK_P$AA24") (pintype "input"))
    )
    (net (code "113") (name "SWDIO") (class "Default")
      (node (ref "J2") (pin "2") (pinfunction "2_2") (pintype "bidirectional"))
      (node (ref "TP_SWDIO") (pin "TP") (pinfunction "TP_TP") (pintype "input"))
      (node (ref "U$1") (pin "P$AC24") (pinfunction "SWDIO_P$AC24") (pintype "bidirectional"))
    )
    (net (code "114") (name "SWO") (class "Default")
      (node (ref "TP_SWO") (pin "TP") (pinfunction "TP_TP") (pintype "input"))
      (node (ref "U$1") (pin "P$AD22") (pinfunction "P1.00_P$AD22") (pintype "bidirectional"))
    )
    (net (code "115") (name "VBAT{slash}1.2A") (class "Default")
      (node (ref "C32") (pin "2") (pinfunction "2_2") (pintype "passive"))
      (node (ref "TP_VBAT") (pin "TP") (pinfunction "TP_TP") (pintype "input"))
      (node (ref "U1") (pin "2") (pinfunction "CELL_2") (pintype "power_in"))
      (node (ref "U1") (pin "3") (pinfunction "VDD_3") (pintype "power_in"))
    )
    (net (code "116") (name "VBAT{slash}2.5C") (class "Default")
      (node (ref "C3") (pin "2") (pinfunction "2_2") (pintype "passive"))
      (node (ref "IC1") (pin "C2") (pinfunction "BAT_C2") (pintype "bidirectional"))
    )
    (net (code "117") (name "VBUS{slash}1.5D") (class "Default")
      (node (ref "C33") (pin "2") (pinfunction "2_2") (pintype "passive"))
      (node (ref "C34") (pin "1") (pinfunction "1_1") (pintype "passive"))
      (node (ref "D4") (pin "5") (pinfunction "VBUS_5") (pintype "bidirectional"))
      (node (ref "J3") (pin "A4_B9") (pinfunction "VBUS_A4_B9") (pintype "power_in"))
      (node (ref "J3") (pin "A9_B4") (pinfunction "VBUS_A9_B4") (pintype "power_in"))
    )
    (net (code "118") (name "VBUS{slash}2.6D") (class "Default")
      (node (ref "C1") (pin "2") (pinfunction "2_2") (pintype "passive"))
      (node (ref "C28") (pin "1") (pinfunction "1_1") (pintype "passive"))
      (node (ref "IC1") (pin "A2") (pinfunction "IN_A2") (pintype "bidirectional"))
      (node (ref "U$1") (pin "P$AD2") (pinfunction "VBUS_P$AD2") (pintype "power_in"))
    )
    (net (code "119") (name "VREG") (class "Default")
      (node (ref "C2") (pin "1") (pinfunction "1_1") (pintype "passive"))
      (node (ref "C38") (pin "1") (pinfunction "1_1") (pintype "passive"))
      (node (ref "C39") (pin "2") (pinfunction "2_2") (pintype "passive"))
      (node (ref "IC1") (pin "B2") (pinfunction "SYS_B2") (pintype "bidirectional"))
      (node (ref "IC2") (pin "A1") (pinfunction "EN_A1") (pintype "bidirectional"))
      (node (ref "IC2") (pin "A2") (pinfunction "VIN_1_A2") (pintype "bidirectional"))
      (node (ref "IC2") (pin "A3") (pinfunction "VIN_2_A3") (pintype "bidirectional"))
      (node (ref "TP_VREG") (pin "TP") (pinfunction "TP_TP") (pintype "input"))
    )
    (net (code "120") (name "unconnected-(ANT1-NC-Pad2)") (class "Default")
      (node (ref "ANT1") (pin "2") (pinfunction "NC_2") (pintype "no_connect"))
    )
    (net (code "121") (name "unconnected-(IC1-GND-PadD2)") (class "Default")
      (node (ref "IC1") (pin "D2") (pinfunction "GND_D2") (pintype "bidirectional"))
    )
    (net (code "122") (name "unconnected-(IC2-PGND_2-PadC3)") (class "Default")
      (node (ref "IC2") (pin "C3") (pinfunction "PGND_2_C3") (pintype "bidirectional"))
    )
    (net (code "123") (name "unconnected-(IC3-ASCL-Pad11)") (class "Default")
      (node (ref "IC3") (pin "11") (pinfunction "ASCL_11") (pintype "bidirectional"))
    )
    (net (code "124") (name "unconnected-(IC3-ASDA-Pad4)") (class "Default")
      (node (ref "IC3") (pin "4") (pinfunction "ASDA_4") (pintype "bidirectional"))
    )
    (net (code "125") (name "unconnected-(J1-Pad1)") (class "Default")
      (node (ref "J1") (pin "1") (pinfunction "1_1") (pintype "bidirectional"))
    )
    (net (code "126") (name "unconnected-(J1-Pad6)") (class "Default")
      (node (ref "J1") (pin "6") (pinfunction "6_6") (pintype "bidirectional"))
    )
    (net (code "127") (name "unconnected-(J1-Pad7)") (class "Default")
      (node (ref "J1") (pin "7") (pinfunction "7_7") (pintype "bidirectional"))
    )
    (net (code "128") (name "unconnected-(J3-SBU1-PadA8)") (class "Default")
      (node (ref "J3") (pin "A8") (pinfunction "SBU1_A8") (pintype "bidirectional"))
    )
    (net (code "129") (name "unconnected-(J3-SBU2-PadB8)") (class "Default")
      (node (ref "J3") (pin "B8") (pinfunction "SBU2_B8") (pintype "bidirectional"))
    )
    (net (code "130") (name "unconnected-(U$1-DCCH-PadP$AB2)") (class "Default")
      (node (ref "U$1") (pin "P$AB2") (pinfunction "DCCH_P$AB2") (pintype "bidirectional"))
    )
  )
)
